# arduino-pro-mini_2-way-switches_v0_2.net
KiCad netlist of a schematic drawn in EAGLE
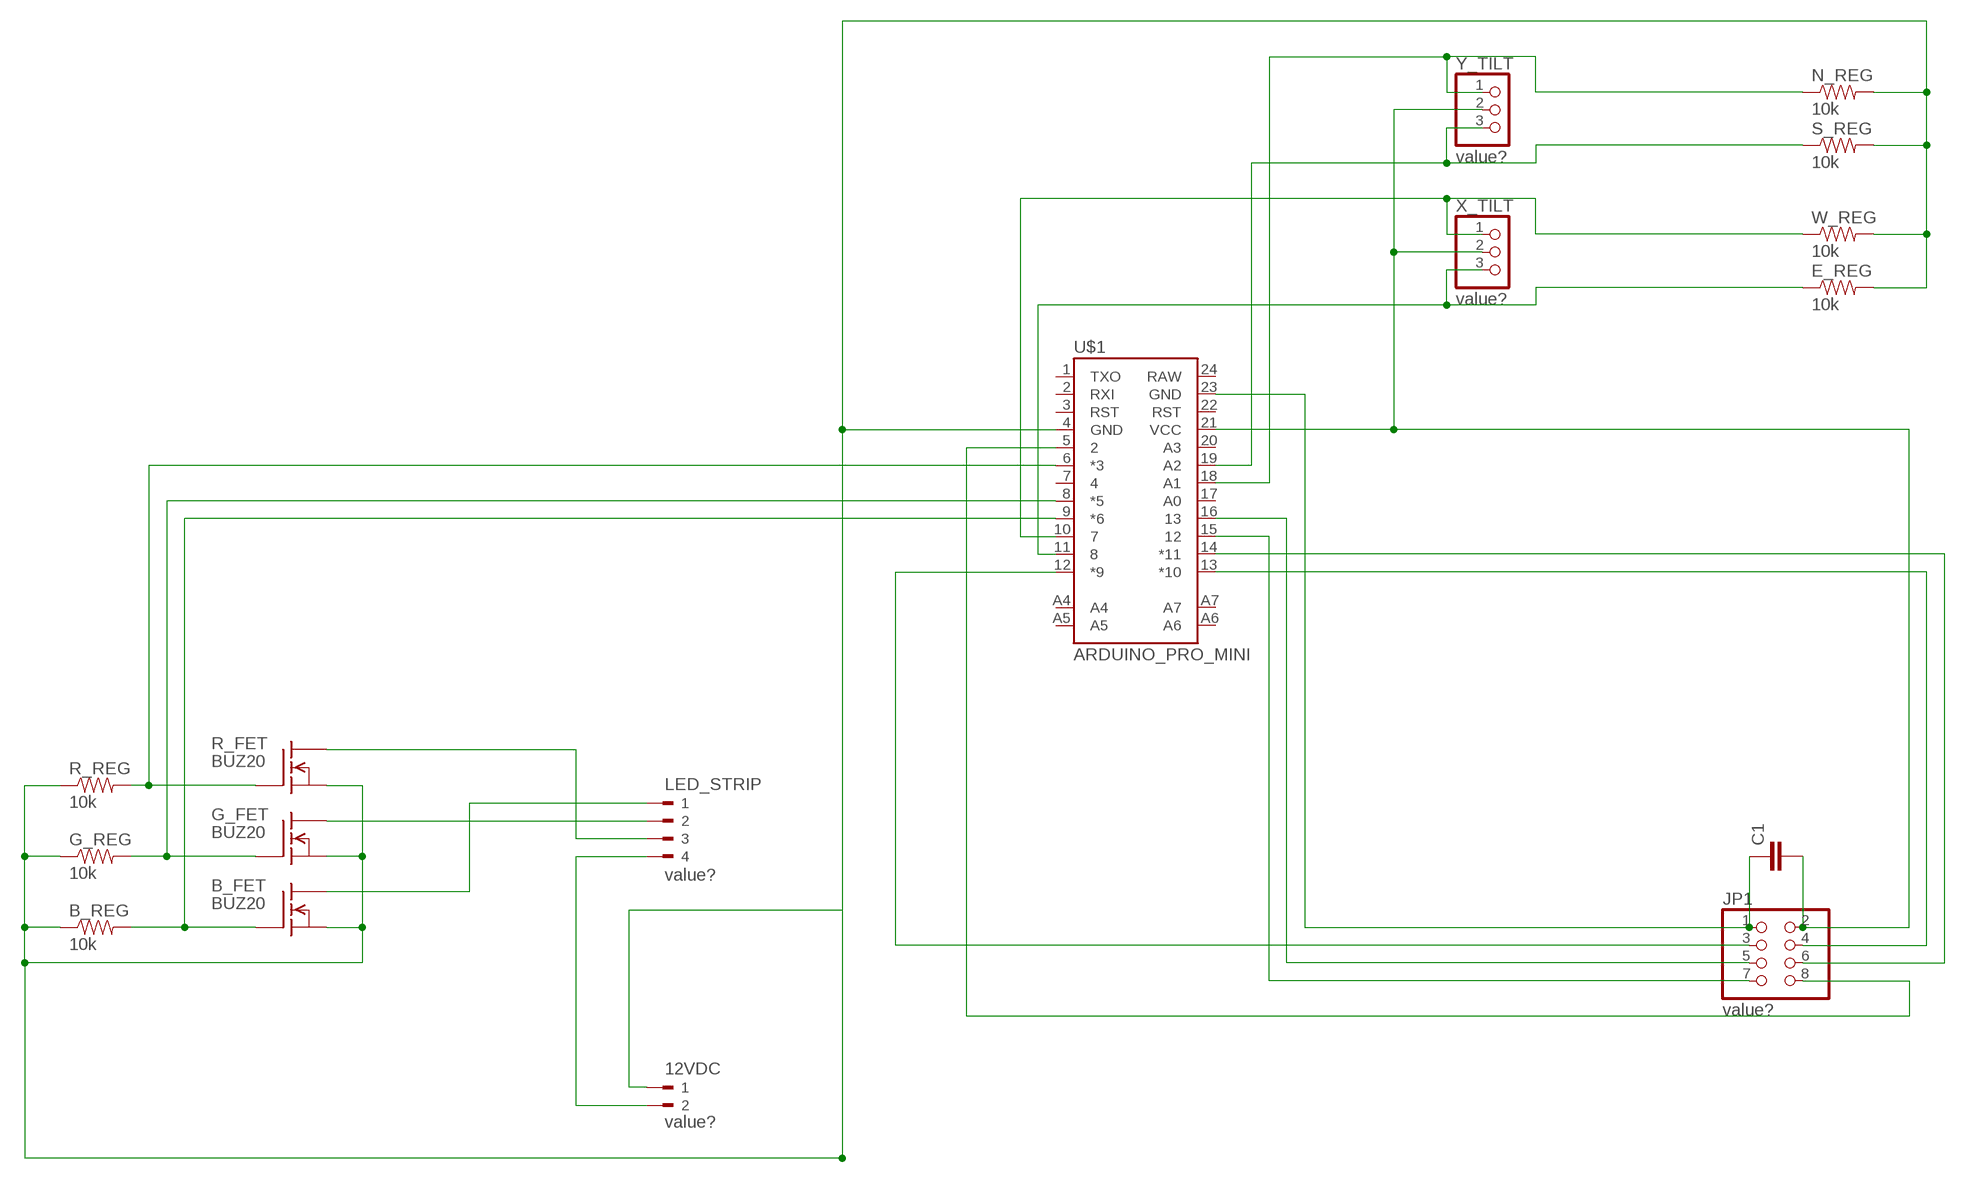
[diagram p0: schematic, sheet 1]

(export (version "E")
  (design (tool "Eeschema 10.0.6"))
  (components
    (comp (ref "12VDC")
      (value "value?")
      (footprint "eagle-import:180-2")
      (libsource (lib "eagle-import") (part "180-2"))
    )
    (comp (ref "B_FET")
      (value "BUZ20")
      (footprint "eagle-import:TO220")
      (libsource (lib "eagle-import") (part "BUZ20"))
    )
    (comp (ref "B_REG")
      (value "10k")
      (footprint "eagle-import:AXIAL-0.4")
      (libsource (lib "eagle-import") (part "RESISTORPTH-1/4W"))
    )
    (comp (ref "C1")
      (value "CAPPTH")
      (footprint "eagle-import:CAP-PTH-SMALL")
      (libsource (lib "eagle-import") (part "CAPPTH"))
    )
    (comp (ref "E_REG")
      (value "10k")
      (footprint "eagle-import:AXIAL-0.4")
      (libsource (lib "eagle-import") (part "RESISTORPTH-1/4W"))
    )
    (comp (ref "G_FET")
      (value "BUZ20")
      (footprint "eagle-import:TO220")
      (libsource (lib "eagle-import") (part "BUZ20"))
    )
    (comp (ref "G_REG")
      (value "10k")
      (footprint "eagle-import:AXIAL-0.4")
      (libsource (lib "eagle-import") (part "RESISTORPTH-1/4W"))
    )
    (comp (ref "JP1")
      (value "value?")
      (footprint "eagle-import:2X04")
      (libsource (lib "eagle-import") (part "PINHD-2X4"))
    )
    (comp (ref "LED_STRIP")
      (value "value?")
      (footprint "eagle-import:180-4")
      (libsource (lib "eagle-import") (part "180-4"))
    )
    (comp (ref "N_REG")
      (value "10k")
      (footprint "eagle-import:AXIAL-0.4")
      (libsource (lib "eagle-import") (part "RESISTORPTH-1/4W"))
    )
    (comp (ref "R_FET")
      (value "BUZ20")
      (footprint "eagle-import:TO220")
      (libsource (lib "eagle-import") (part "BUZ20"))
    )
    (comp (ref "R_REG")
      (value "10k")
      (footprint "eagle-import:AXIAL-0.4")
      (libsource (lib "eagle-import") (part "RESISTORPTH-1/4W"))
    )
    (comp (ref "S_REG")
      (value "10k")
      (footprint "eagle-import:AXIAL-0.4")
      (libsource (lib "eagle-import") (part "RESISTORPTH-1/4W"))
    )
    (comp (ref "U$1")
      (value "ARDUINO_PRO_MINI")
      (footprint "eagle-import:ARDUINO_PRO_MINI")
      (libsource (lib "eagle-import") (part "ARDUINO_PRO_MINI"))
    )
    (comp (ref "W_REG")
      (value "10k")
      (footprint "eagle-import:AXIAL-0.4")
      (libsource (lib "eagle-import") (part "RESISTORPTH-1/4W"))
    )
    (comp (ref "X_TILT")
      (value "value?")
      (footprint "eagle-import:1X03")
      (libsource (lib "eagle-import") (part "PINHD-1X3"))
    )
    (comp (ref "Y_TILT")
      (value "value?")
      (footprint "eagle-import:1X03")
      (libsource (lib "eagle-import") (part "PINHD-1X3"))
    )
  )
  (nets
    (net (code "1") (name "Net-(12VDC-Pad2)") (class "Default")
      (node (ref "12VDC") (pin "2") (pinfunction "2_2") (pintype "passive"))
      (node (ref "LED_STRIP") (pin "4") (pinfunction "4_4") (pintype "passive"))
    )
    (net (code "2") (name "Net-(B_FET-D)") (class "Default")
      (node (ref "B_FET") (pin "2") (pinfunction "D_2") (pintype "passive"))
      (node (ref "LED_STRIP") (pin "1") (pinfunction "1_1") (pintype "passive"))
    )
    (net (code "3") (name "Net-(B_FET-G)") (class "Default")
      (node (ref "B_FET") (pin "1") (pinfunction "G_1") (pintype "passive"))
      (node (ref "B_REG") (pin "P$2") (pinfunction "2_P$2") (pintype "passive"))
      (node (ref "U$1") (pin "9") (pinfunction "*6_9") (pintype "bidirectional"))
    )
    (net (code "4") (name "Net-(B_FET-S)") (class "Default")
      (node (ref "12VDC") (pin "1") (pinfunction "1_1") (pintype "passive"))
      (node (ref "B_FET") (pin "3") (pinfunction "S_3") (pintype "passive"))
      (node (ref "B_REG") (pin "P$1") (pinfunction "1_P$1") (pintype "passive"))
      (node (ref "E_REG") (pin "P$2") (pinfunction "2_P$2") (pintype "passive"))
      (node (ref "G_FET") (pin "3") (pinfunction "S_3") (pintype "passive"))
      (node (ref "G_REG") (pin "P$1") (pinfunction "1_P$1") (pintype "passive"))
      (node (ref "N_REG") (pin "P$2") (pinfunction "2_P$2") (pintype "passive"))
      (node (ref "R_FET") (pin "3") (pinfunction "S_3") (pintype "passive"))
      (node (ref "R_REG") (pin "P$1") (pinfunction "1_P$1") (pintype "passive"))
      (node (ref "S_REG") (pin "P$2") (pinfunction "2_P$2") (pintype "passive"))
      (node (ref "U$1") (pin "4") (pinfunction "GND_4") (pintype "bidirectional"))
      (node (ref "W_REG") (pin "P$2") (pinfunction "2_P$2") (pintype "passive"))
    )
    (net (code "5") (name "Net-(C1-Pad1)") (class "Default")
      (node (ref "C1") (pin "1") (pinfunction "1_1") (pintype "passive"))
      (node (ref "JP1") (pin "1") (pinfunction "1_1") (pintype "passive"))
      (node (ref "U$1") (pin "23") (pinfunction "GND_23") (pintype "bidirectional"))
    )
    (net (code "6") (name "Net-(E_REG-1)") (class "Default")
      (node (ref "E_REG") (pin "P$1") (pinfunction "1_P$1") (pintype "passive"))
      (node (ref "U$1") (pin "11") (pinfunction "8_11") (pintype "bidirectional"))
      (node (ref "X_TILT") (pin "3") (pinfunction "3_3") (pintype "passive"))
    )
    (net (code "7") (name "Net-(G_FET-D)") (class "Default")
      (node (ref "G_FET") (pin "2") (pinfunction "D_2") (pintype "passive"))
      (node (ref "LED_STRIP") (pin "2") (pinfunction "2_2") (pintype "passive"))
    )
    (net (code "8") (name "Net-(G_FET-G)") (class "Default")
      (node (ref "G_FET") (pin "1") (pinfunction "G_1") (pintype "passive"))
      (node (ref "G_REG") (pin "P$2") (pinfunction "2_P$2") (pintype "passive"))
      (node (ref "U$1") (pin "8") (pinfunction "*5_8") (pintype "bidirectional"))
    )
    (net (code "9") (name "Net-(N_REG-1)") (class "Default")
      (node (ref "N_REG") (pin "P$1") (pinfunction "1_P$1") (pintype "passive"))
      (node (ref "U$1") (pin "18") (pinfunction "A1_18") (pintype "bidirectional"))
      (node (ref "Y_TILT") (pin "1") (pinfunction "1_1") (pintype "passive"))
    )
    (net (code "10") (name "Net-(R_FET-D)") (class "Default")
      (node (ref "LED_STRIP") (pin "3") (pinfunction "3_3") (pintype "passive"))
      (node (ref "R_FET") (pin "2") (pinfunction "D_2") (pintype "passive"))
    )
    (net (code "11") (name "Net-(R_FET-G)") (class "Default")
      (node (ref "R_FET") (pin "1") (pinfunction "G_1") (pintype "passive"))
      (node (ref "R_REG") (pin "P$2") (pinfunction "2_P$2") (pintype "passive"))
      (node (ref "U$1") (pin "6") (pinfunction "*3_6") (pintype "bidirectional"))
    )
    (net (code "12") (name "Net-(S_REG-1)") (class "Default")
      (node (ref "S_REG") (pin "P$1") (pinfunction "1_P$1") (pintype "passive"))
      (node (ref "U$1") (pin "19") (pinfunction "A2_19") (pintype "bidirectional"))
      (node (ref "Y_TILT") (pin "3") (pinfunction "3_3") (pintype "passive"))
    )
    (net (code "13") (name "Net-(U$1-*9)") (class "Default")
      (node (ref "JP1") (pin "3") (pinfunction "3_3") (pintype "passive"))
      (node (ref "U$1") (pin "12") (pinfunction "*9_12") (pintype "bidirectional"))
    )
    (net (code "14") (name "Net-(U$1-*10)") (class "Default")
      (node (ref "JP1") (pin "4") (pinfunction "4_4") (pintype "passive"))
      (node (ref "U$1") (pin "13") (pinfunction "*10_13") (pintype "bidirectional"))
    )
    (net (code "15") (name "Net-(U$1-*11)") (class "Default")
      (node (ref "JP1") (pin "6") (pinfunction "6_6") (pintype "passive"))
      (node (ref "U$1") (pin "14") (pinfunction "*11_14") (pintype "bidirectional"))
    )
    (net (code "16") (name "Net-(U$1-2)") (class "Default")
      (node (ref "JP1") (pin "8") (pinfunction "8_8") (pintype "passive"))
      (node (ref "U$1") (pin "5") (pinfunction "2_5") (pintype "bidirectional"))
    )
    (net (code "17") (name "Net-(U$1-7)") (class "Default")
      (node (ref "U$1") (pin "10") (pinfunction "7_10") (pintype "bidirectional"))
      (node (ref "W_REG") (pin "P$1") (pinfunction "1_P$1") (pintype "passive"))
      (node (ref "X_TILT") (pin "1") (pinfunction "1_1") (pintype "passive"))
    )
    (net (code "18") (name "Net-(U$1-12)") (class "Default")
      (node (ref "JP1") (pin "7") (pinfunction "7_7") (pintype "passive"))
      (node (ref "U$1") (pin "15") (pinfunction "12_15") (pintype "bidirectional"))
    )
    (net (code "19") (name "Net-(U$1-13)") (class "Default")
      (node (ref "JP1") (pin "5") (pinfunction "5_5") (pintype "passive"))
      (node (ref "U$1") (pin "16") (pinfunction "13_16") (pintype "bidirectional"))
    )
    (net (code "20") (name "Net-(U$1-VCC)") (class "Default")
      (node (ref "C1") (pin "2") (pinfunction "2_2") (pintype "passive"))
      (node (ref "JP1") (pin "2") (pinfunction "2_2") (pintype "passive"))
      (node (ref "U$1") (pin "21") (pinfunction "VCC_21") (pintype "bidirectional"))
      (node (ref "X_TILT") (pin "2") (pinfunction "2_2") (pintype "passive"))
      (node (ref "Y_TILT") (pin "2") (pinfunction "2_2") (pintype "passive"))
    )
    (net (code "21") (name "unconnected-(U$1-4-Pad7)") (class "Default")
      (node (ref "U$1") (pin "7") (pinfunction "4_7") (pintype "bidirectional"))
    )
    (net (code "22") (name "unconnected-(U$1-A0-Pad17)") (class "Default")
      (node (ref "U$1") (pin "17") (pinfunction "A0_17") (pintype "bidirectional"))
    )
    (net (code "23") (name "unconnected-(U$1-A3-Pad20)") (class "Default")
      (node (ref "U$1") (pin "20") (pinfunction "A3_20") (pintype "bidirectional"))
    )
    (net (code "24") (name "unconnected-(U$1-PadA4)") (class "Default")
      (node (ref "U$1") (pin "A4") (pinfunction "A4_A4") (pintype "bidirectional"))
    )
    (net (code "25") (name "unconnected-(U$1-PadA5)") (class "Default")
      (node (ref "U$1") (pin "A5") (pinfunction "A5_A5") (pintype "bidirectional"))
    )
    (net (code "26") (name "unconnected-(U$1-PadA6)") (class "Default")
      (node (ref "U$1") (pin "A6") (pinfunction "A6_A6") (pintype "bidirectional"))
    )
    (net (code "27") (name "unconnected-(U$1-PadA7)") (class "Default")
      (node (ref "U$1") (pin "A7") (pinfunction "A7_A7") (pintype "bidirectional"))
    )
    (net (code "28") (name "unconnected-(U$1-RAW-Pad24)") (class "Default")
      (node (ref "U$1") (pin "24") (pinfunction "RAW_24") (pintype "bidirectional"))
    )
    (net (code "29") (name "unconnected-(U$1-RST-Pad3)") (class "Default")
      (node (ref "U$1") (pin "3") (pinfunction "RST_3") (pintype "bidirectional"))
    )
    (net (code "30") (name "unconnected-(U$1-RST-Pad22)") (class "Default")
      (node (ref "U$1") (pin "22") (pinfunction "RST_22") (pintype "bidirectional"))
    )
    (net (code "31") (name "unconnected-(U$1-RXI-Pad2)") (class "Default")
      (node (ref "U$1") (pin "2") (pinfunction "RXI_2") (pintype "bidirectional"))
    )
    (net (code "32") (name "unconnected-(U$1-TXO-Pad1)") (class "Default")
      (node (ref "U$1") (pin "1") (pinfunction "TXO_1") (pintype "bidirectional"))
    )
  )
)
